# ENEL400_Project_2021-03-30.net
KiCad netlist of a schematic drawn in EasyEDA
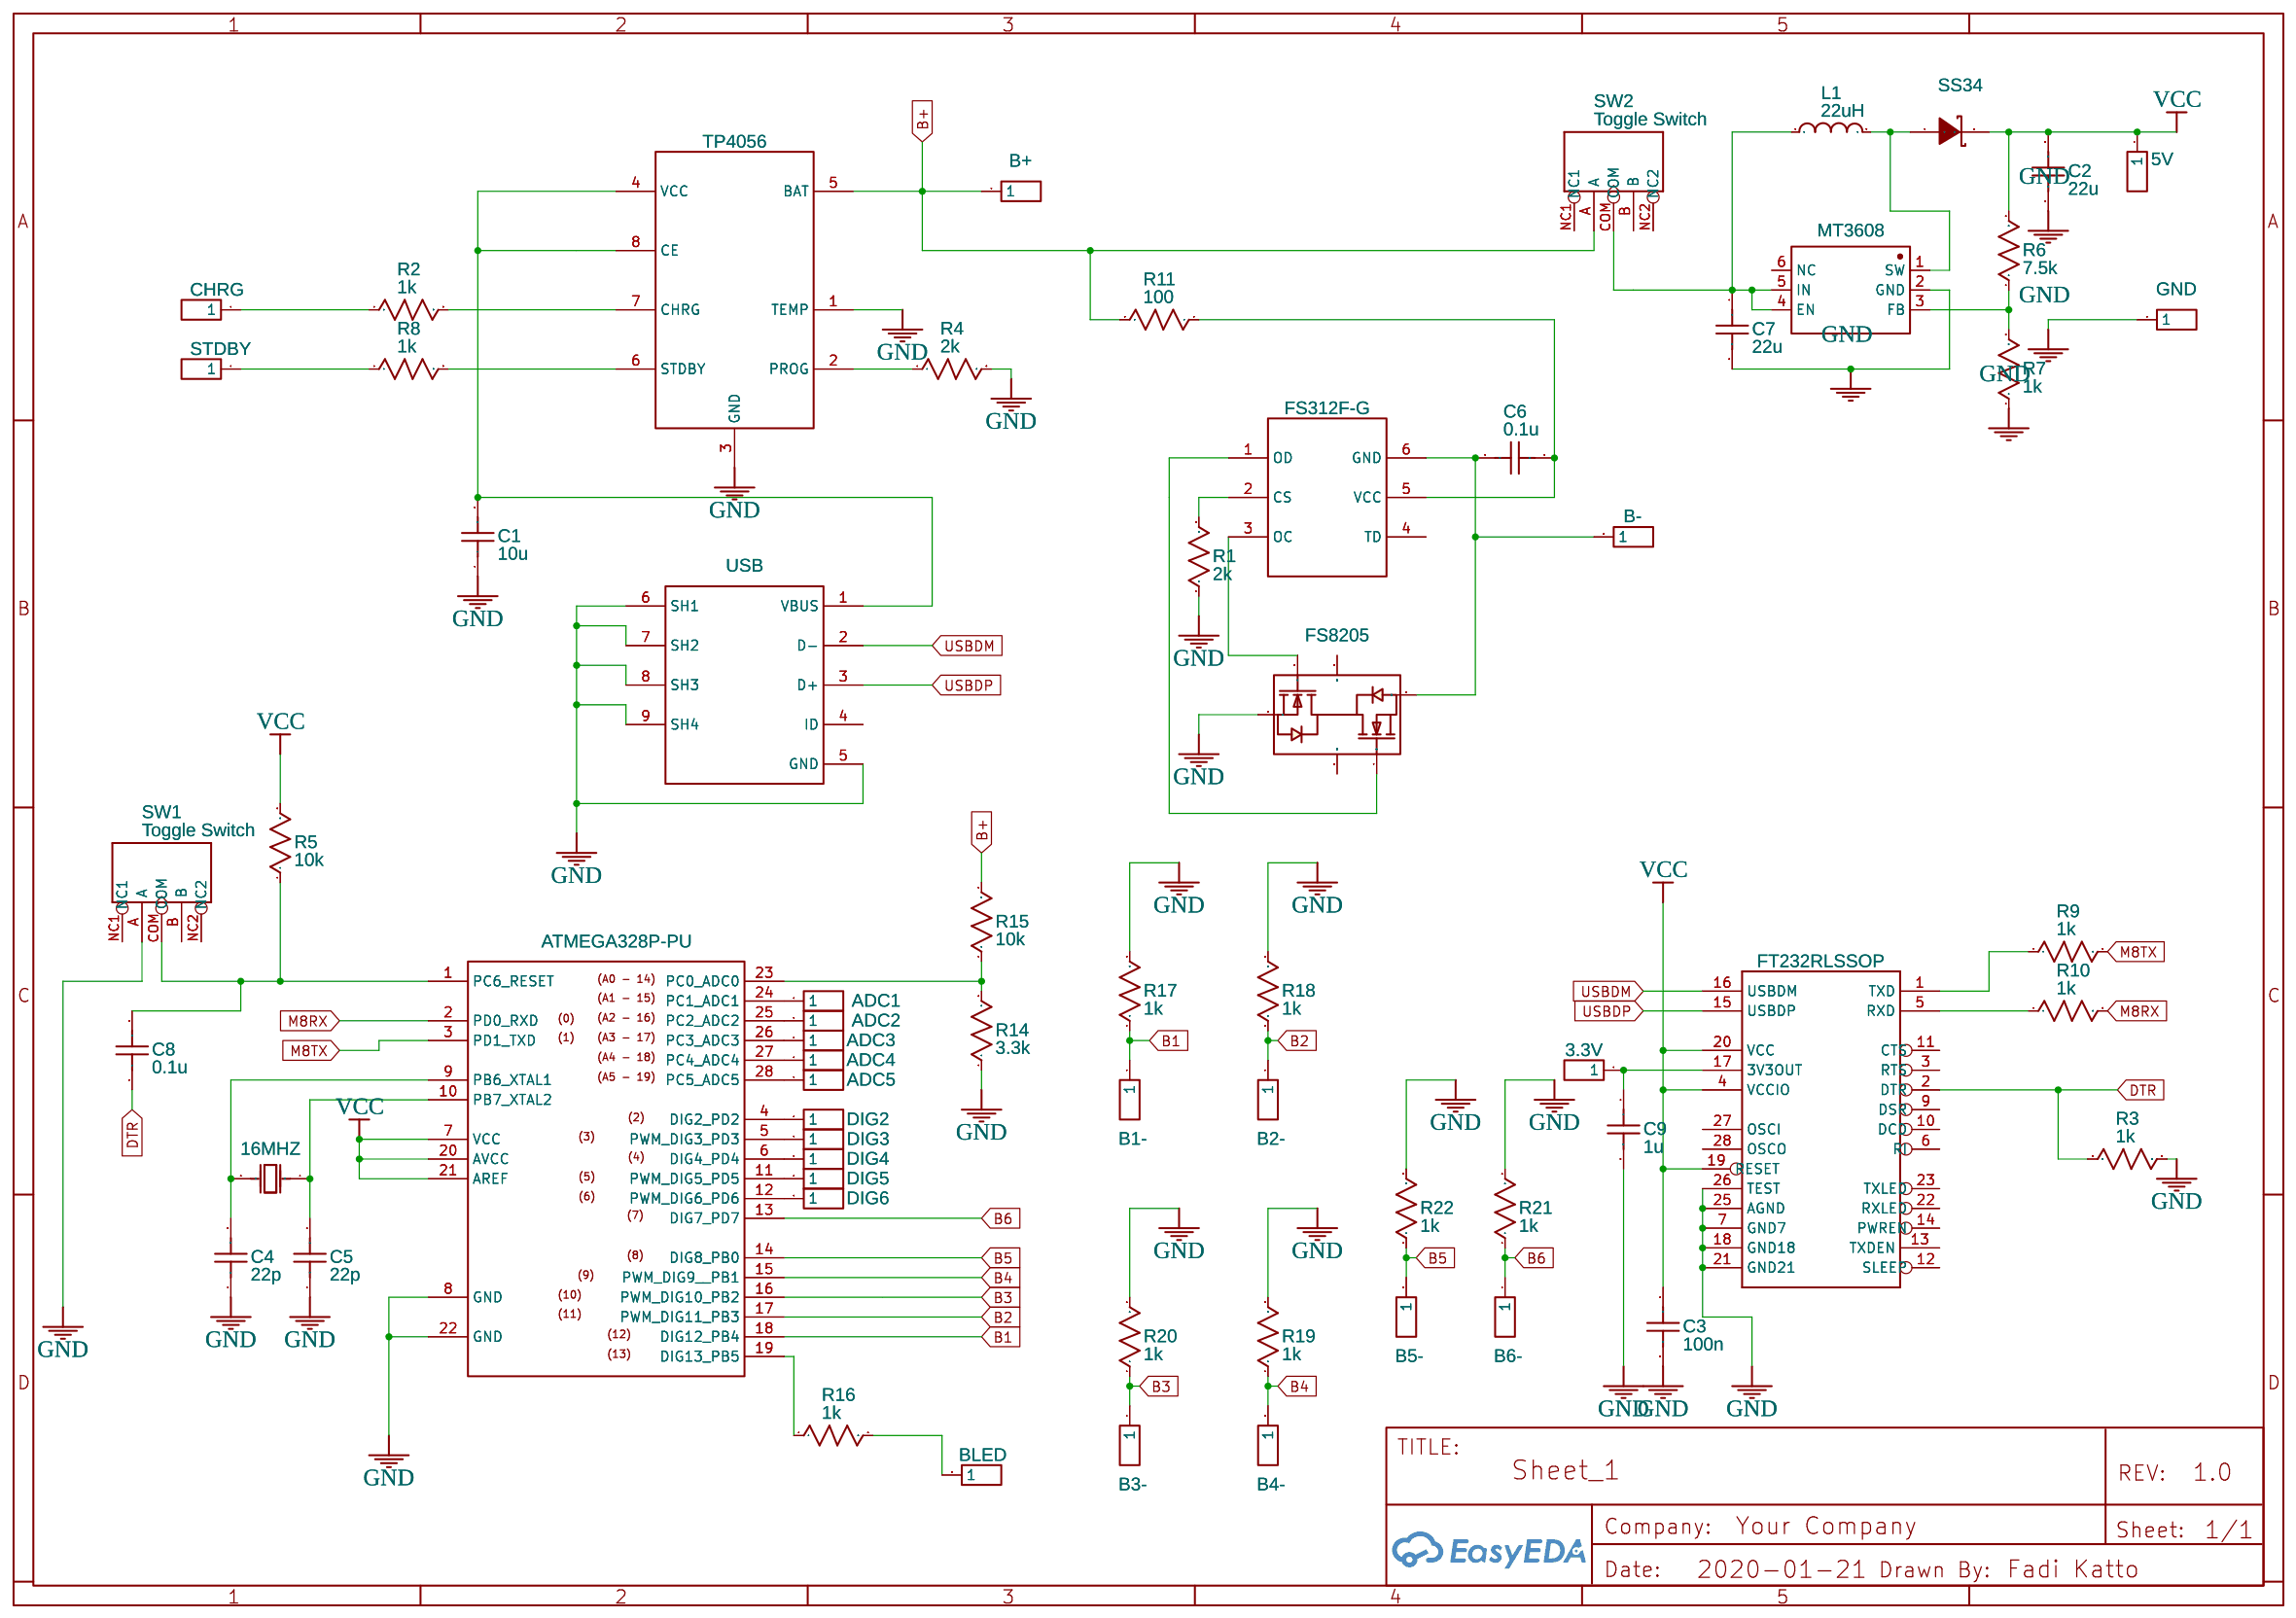
[diagram p0: schematic sheet]

(export (version "E")
  (design (tool "Eeschema 10.0.6"))
  (components
    (comp (ref "3.3V")
      (value "Header-Male-2.54_1x1")
      (fields (field (name "BOM_Supplier Part") "C81276"))
      (libsource (lib "") (part "Header-Male-2.54_1x1_4"))
    )
    (comp (ref "5V")
      (value "Header-Male-2.54_1x1")
      (fields (field (name "BOM_Supplier Part") "C81276"))
      (libsource (lib "") (part "Header-Male-2.54_1x1_3"))
    )
    (comp (ref "16MHZ")
      (value "16MHZ")
      (fields
        (field (name "BOM_Manufacturer Part") "X49SD16MSD2SC")
        (field (name "BOM_Supplier Part") "C16212")
      )
      (libsource (lib "") (part "16MHZ"))
    )
    (comp (ref "ADC1")
      (value "Header-Male-2.54_1x1")
      (fields (field (name "BOM_Supplier Part") "C81276"))
      (libsource (lib "") (part "Header-Male-2.54_1x1"))
    )
    (comp (ref "ADC2")
      (value "Header-Male-2.54_1x1")
      (fields (field (name "BOM_Supplier Part") "C81276"))
      (libsource (lib "") (part "Header-Male-2.54_1x1"))
    )
    (comp (ref "ADC3")
      (value "Header-Male-2.54_1x1")
      (fields (field (name "BOM_Supplier Part") "C81276"))
      (libsource (lib "") (part "Header-Male-2.54_1x1"))
    )
    (comp (ref "ADC4")
      (value "Header-Male-2.54_1x1")
      (fields (field (name "BOM_Supplier Part") "C81276"))
      (libsource (lib "") (part "Header-Male-2.54_1x1"))
    )
    (comp (ref "ADC5")
      (value "Header-Male-2.54_1x1")
      (fields (field (name "BOM_Supplier Part") "C81276"))
      (libsource (lib "") (part "Header-Male-2.54_1x1"))
    )
    (comp (ref "ATMEGA328P-PU")
      (value "ATMEGA328P-PU")
      (fields (field (name "BOM_Supplier Part") "C33901"))
      (libsource (lib "") (part "ATMEGA328P-PU"))
    )
    (comp (ref "B+")
      (value "Header-Male-2.54_1x1")
      (fields (field (name "BOM_Supplier Part") "C81276"))
      (libsource (lib "") (part "Header-Male-2.54_1x1_14"))
    )
    (comp (ref "B-")
      (value "Header-Male-2.54_1x1")
      (fields (field (name "BOM_Supplier Part") "C81276"))
      (libsource (lib "") (part "Header-Male-2.54_1x1_6"))
    )
    (comp (ref "B1-")
      (value "Header-Male-2.54_1x1")
      (fields (field (name "BOM_Supplier Part") "C81276"))
      (libsource (lib "") (part "Header-Male-2.54_1x1_8"))
    )
    (comp (ref "B2-")
      (value "Header-Male-2.54_1x1")
      (fields (field (name "BOM_Supplier Part") "C81276"))
      (libsource (lib "") (part "Header-Male-2.54_1x1_5"))
    )
    (comp (ref "B3-")
      (value "Header-Male-2.54_1x1")
      (fields (field (name "BOM_Supplier Part") "C81276"))
      (libsource (lib "") (part "Header-Male-2.54_1x1_7"))
    )
    (comp (ref "B4-")
      (value "Header-Male-2.54_1x1")
      (fields (field (name "BOM_Supplier Part") "C81276"))
      (libsource (lib "") (part "Header-Male-2.54_1x1_2"))
    )
    (comp (ref "B5-")
      (value "Header-Male-2.54_1x1")
      (fields (field (name "BOM_Supplier Part") "C81276"))
      (libsource (lib "") (part "Header-Male-2.54_1x1_10"))
    )
    (comp (ref "B6-")
      (value "Header-Male-2.54_1x1")
      (fields (field (name "BOM_Supplier Part") "C81276"))
      (libsource (lib "") (part "Header-Male-2.54_1x1_12"))
    )
    (comp (ref "BLED")
      (value "Header-Male-2.54_1x1")
      (fields (field (name "BOM_Supplier Part") "C81276"))
      (libsource (lib "") (part "Header-Male-2.54_1x1_15"))
    )
    (comp (ref "C1") (value "10u") (libsource (lib "") (part "Cap_0805_US_1")))
    (comp (ref "C2") (value "22u") (libsource (lib "") (part "Cap_0805_US_1")))
    (comp (ref "C3") (value "100n") (libsource (lib "") (part "Cap_0805_US")))
    (comp (ref "C4") (value "22p") (libsource (lib "") (part "Cap_0805_US_1")))
    (comp (ref "C5") (value "22p") (libsource (lib "") (part "Cap_0805_US_1")))
    (comp (ref "C6") (value "0.1u") (libsource (lib "") (part "Cap_0805_US_2")))
    (comp (ref "C7") (value "22u") (libsource (lib "") (part "Cap_0805_US")))
    (comp (ref "C8") (value "0.1u") (libsource (lib "") (part "Cap_0805_US_1")))
    (comp (ref "C9") (value "1u") (libsource (lib "") (part "Cap_0805_US")))
    (comp (ref "CHRG")
      (value "Header-Male-2.54_1x1")
      (fields (field (name "BOM_Supplier Part") "C81276"))
      (libsource (lib "") (part "Header-Male-2.54_1x1_13"))
    )
    (comp (ref "DIG2")
      (value "Header-Male-2.54_1x1")
      (fields (field (name "BOM_Supplier Part") "C81276"))
      (libsource (lib "") (part "Header-Male-2.54_1x1_1"))
    )
    (comp (ref "DIG3")
      (value "Header-Male-2.54_1x1")
      (fields (field (name "BOM_Supplier Part") "C81276"))
      (libsource (lib "") (part "Header-Male-2.54_1x1_1"))
    )
    (comp (ref "DIG4")
      (value "Header-Male-2.54_1x1")
      (fields (field (name "BOM_Supplier Part") "C81276"))
      (libsource (lib "") (part "Header-Male-2.54_1x1_1"))
    )
    (comp (ref "DIG5")
      (value "Header-Male-2.54_1x1")
      (fields (field (name "BOM_Supplier Part") "C81276"))
      (libsource (lib "") (part "Header-Male-2.54_1x1_1"))
    )
    (comp (ref "DIG6")
      (value "Header-Male-2.54_1x1")
      (fields (field (name "BOM_Supplier Part") "C81276"))
      (libsource (lib "") (part "Header-Male-2.54_1x1_1"))
    )
    (comp (ref "FS312F-G")
      (value "FS312F-G")
      (fields (field (name "BOM_Manufacturer Part") "DW01+G") (field (name "BOM_Supplier Part") "C14213"))
      (libsource (lib "") (part "Unknown_690_-525"))
    )
    (comp (ref "FS8205")
      (value "FS8205")
      (fields (field (name "BOM_Supplier Part") "C32254"))
      (libsource (lib "") (part "Unknown_725_-375"))
    )
    (comp (ref "FT232RLSSOP") (value "FT232RLSSOP") (libsource (lib "") (part "FT232RLSSOP")))
    (comp (ref "GND")
      (value "Header-Male-2.54_1x1")
      (fields (field (name "BOM_Supplier Part") "C81276"))
      (libsource (lib "") (part "Header-Male-2.54_1x1_11"))
    )
    (comp (ref "L1") (value "22uH") (libsource (lib "") (part "Inductor_0805_US")))
    (comp (ref "MT3608")
      (value "MT3608")
      (fields (field (name "BOM_Supplier Part") "C84817"))
      (libsource (lib "") (part "Unknown_995_-610"))
    )
    (comp (ref "R1") (value "2k") (libsource (lib "") (part "Res_0805(1/8W)_US")))
    (comp (ref "R2") (value "1k") (libsource (lib "") (part "Res_0805(1/8W)_US_1")))
    (comp (ref "R3") (value "1k") (libsource (lib "") (part "Res_0805(1/8W)_US_1")))
    (comp (ref "R4") (value "2k") (libsource (lib "") (part "Res_0805(1/8W)_US_1")))
    (comp (ref "R5") (value "10k") (libsource (lib "") (part "Res_0805(1/8W)_US")))
    (comp (ref "R6") (value "7.5k") (libsource (lib "") (part "Res_0805(1/8W)_US")))
    (comp (ref "R7") (value "1k") (libsource (lib "") (part "Res_0805(1/8W)_US")))
    (comp (ref "R8") (value "1k") (libsource (lib "") (part "Res_0805(1/8W)_US_1")))
    (comp (ref "R9") (value "1k") (libsource (lib "") (part "Res_0805(1/8W)_US_1")))
    (comp (ref "R10") (value "1k") (libsource (lib "") (part "Res_0805(1/8W)_US_1")))
    (comp (ref "R11") (value "100") (libsource (lib "") (part "Res_0805(1/8W)_US_2")))
    (comp (ref "R14") (value "3.3k") (libsource (lib "") (part "Res_0805(1/8W)_US")))
    (comp (ref "R15") (value "10k") (libsource (lib "") (part "Res_0805(1/8W)_US")))
    (comp (ref "R16") (value "1k") (libsource (lib "") (part "Res_0805(1/8W)_US_1")))
    (comp (ref "R17") (value "1k") (libsource (lib "") (part "Res_0805(1/8W)_US")))
    (comp (ref "R18") (value "1k") (libsource (lib "") (part "Res_0805(1/8W)_US")))
    (comp (ref "R19") (value "1k") (libsource (lib "") (part "Res_0805(1/8W)_US")))
    (comp (ref "R20") (value "1k") (libsource (lib "") (part "Res_0805(1/8W)_US")))
    (comp (ref "R21") (value "1k") (libsource (lib "") (part "Res_0805(1/8W)_US")))
    (comp (ref "R22") (value "1k") (libsource (lib "") (part "Res_0805(1/8W)_US")))
    (comp (ref "SS34")
      (value "SS34")
      (fields (field (name "BOM_Supplier Part") "C8678"))
      (libsource (lib "") (part "Unknown_1035_-670"))
    )
    (comp (ref "STDBY")
      (value "Header-Male-2.54_1x1")
      (fields (field (name "BOM_Supplier Part") "C81276"))
      (libsource (lib "") (part "Header-Male-2.54_1x1_9"))
    )
    (comp (ref "SW1")
      (value "Toggle Switch")
      (fields (field (name "BOM_Manufacturer Part") "3P-2.0-90D-REINFORCE;"))
      (libsource (lib "") (part "Unknown_130_-300"))
    )
    (comp (ref "SW2")
      (value "Toggle Switch")
      (fields (field (name "BOM_Manufacturer Part") "3P-2.0-90D-REINFORCE;"))
      (libsource (lib "") (part "Unknown_865_-660"))
    )
    (comp (ref "TP4056")
      (value "TP4056")
      (fields (field (name "BOM_Supplier Part") "C16581"))
      (libsource (lib "") (part "Unknown_420_-580"))
    )
    (comp (ref "USB") (value "USB - Mini USB") (libsource (lib "") (part "USB - Mini USB")))
  )
  (nets
    (net (code "1") (name "B+") (class "Default")
      (node (ref "B+") (pin "1") (pinfunction "1_1") (pintype "input"))
      (node (ref "R11") (pin "2") (pinfunction "2_2") (pintype "unspecified"))
      (node (ref "R15") (pin "2") (pinfunction "2_2") (pintype "unspecified"))
      (node (ref "SW2") (pin "A") (pinfunction "A_A") (pintype "unspecified"))
      (node (ref "TP4056") (pin "5") (pinfunction "BAT_5") (pintype "unspecified"))
    )
    (net (code "2") (name "B1") (class "Default")
      (node (ref "ATMEGA328P-PU") (pin "18") (pinfunction "DIG12_PB4_18") (pintype "bidirectional"))
      (node (ref "B1-") (pin "1") (pinfunction "1_1") (pintype "input"))
      (node (ref "R17") (pin "1") (pinfunction "1_1") (pintype "unspecified"))
    )
    (net (code "3") (name "B2") (class "Default")
      (node (ref "ATMEGA328P-PU") (pin "17") (pinfunction "PWM_DIG11_PB3_17") (pintype "bidirectional"))
      (node (ref "B2-") (pin "1") (pinfunction "1_1") (pintype "input"))
      (node (ref "R18") (pin "1") (pinfunction "1_1") (pintype "unspecified"))
    )
    (net (code "4") (name "B3") (class "Default")
      (node (ref "ATMEGA328P-PU") (pin "16") (pinfunction "PWM_DIG10_PB2_16") (pintype "bidirectional"))
      (node (ref "B3-") (pin "1") (pinfunction "1_1") (pintype "input"))
      (node (ref "R20") (pin "1") (pinfunction "1_1") (pintype "unspecified"))
    )
    (net (code "5") (name "B4") (class "Default")
      (node (ref "ATMEGA328P-PU") (pin "15") (pinfunction "PWM_DIG9__PB1_15") (pintype "bidirectional"))
      (node (ref "B4-") (pin "1") (pinfunction "1_1") (pintype "input"))
      (node (ref "R19") (pin "1") (pinfunction "1_1") (pintype "unspecified"))
    )
    (net (code "6") (name "B5") (class "Default")
      (node (ref "ATMEGA328P-PU") (pin "14") (pinfunction "DIG8_PB0_14") (pintype "bidirectional"))
      (node (ref "B5-") (pin "1") (pinfunction "1_1") (pintype "input"))
      (node (ref "R22") (pin "1") (pinfunction "1_1") (pintype "unspecified"))
    )
    (net (code "7") (name "B6") (class "Default")
      (node (ref "ATMEGA328P-PU") (pin "13") (pinfunction "DIG7_PD7_13") (pintype "bidirectional"))
      (node (ref "B6-") (pin "1") (pinfunction "1_1") (pintype "input"))
      (node (ref "R21") (pin "1") (pinfunction "1_1") (pintype "unspecified"))
    )
    (net (code "8") (name "DTR") (class "Default")
      (node (ref "C8") (pin "1") (pinfunction "1_1") (pintype "unspecified"))
      (node (ref "FT232RLSSOP") (pin "2") (pinfunction "DTR_2") (pintype "output"))
      (node (ref "R3") (pin "1") (pinfunction "1_1") (pintype "unspecified"))
    )
    (net (code "9") (name "GND") (class "Default")
      (node (ref "ATMEGA328P-PU") (pin "22") (pinfunction "GND_22") (pintype "passive"))
      (node (ref "ATMEGA328P-PU") (pin "8") (pinfunction "GND_8") (pintype "passive"))
      (node (ref "C1") (pin "1") (pinfunction "1_1") (pintype "unspecified"))
      (node (ref "C2") (pin "1") (pinfunction "1_1") (pintype "unspecified"))
      (node (ref "C3") (pin "2") (pinfunction "2_2") (pintype "unspecified"))
      (node (ref "C4") (pin "1") (pinfunction "1_1") (pintype "unspecified"))
      (node (ref "C5") (pin "1") (pinfunction "1_1") (pintype "unspecified"))
      (node (ref "C7") (pin "2") (pinfunction "2_2") (pintype "unspecified"))
      (node (ref "C9") (pin "2") (pinfunction "2_2") (pintype "unspecified"))
      (node (ref "FS8205") (pin "1") (pinfunction "S1_1") (pintype "unspecified"))
      (node (ref "FT232RLSSOP") (pin "18") (pinfunction "GND18_18") (pintype "passive"))
      (node (ref "FT232RLSSOP") (pin "21") (pinfunction "GND21_21") (pintype "passive"))
      (node (ref "FT232RLSSOP") (pin "25") (pinfunction "AGND_25") (pintype "passive"))
      (node (ref "FT232RLSSOP") (pin "26") (pinfunction "TEST_26") (pintype "input"))
      (node (ref "FT232RLSSOP") (pin "7") (pinfunction "GND7_7") (pintype "passive"))
      (node (ref "GND") (pin "1") (pinfunction "1_1") (pintype "input"))
      (node (ref "MT3608") (pin "2") (pinfunction "GND_2") (pintype "unspecified"))
      (node (ref "R1") (pin "1") (pinfunction "1_1") (pintype "unspecified"))
      (node (ref "R14") (pin "1") (pinfunction "1_1") (pintype "unspecified"))
      (node (ref "R17") (pin "2") (pinfunction "2_2") (pintype "unspecified"))
      (node (ref "R18") (pin "2") (pinfunction "2_2") (pintype "unspecified"))
      (node (ref "R19") (pin "2") (pinfunction "2_2") (pintype "unspecified"))
      (node (ref "R20") (pin "2") (pinfunction "2_2") (pintype "unspecified"))
      (node (ref "R21") (pin "2") (pinfunction "2_2") (pintype "unspecified"))
      (node (ref "R22") (pin "2") (pinfunction "2_2") (pintype "unspecified"))
      (node (ref "R3") (pin "2") (pinfunction "2_2") (pintype "unspecified"))
      (node (ref "R4") (pin "2") (pinfunction "2_2") (pintype "unspecified"))
      (node (ref "R7") (pin "1") (pinfunction "1_1") (pintype "unspecified"))
      (node (ref "SW1") (pin "A") (pinfunction "A_A") (pintype "unspecified"))
      (node (ref "TP4056") (pin "1") (pinfunction "TEMP_1") (pintype "unspecified"))
      (node (ref "TP4056") (pin "3") (pinfunction "GND_3") (pintype "unspecified"))
      (node (ref "USB") (pin "5") (pinfunction "GND_5") (pintype "passive"))
      (node (ref "USB") (pin "6") (pinfunction "SH1_6") (pintype "passive"))
      (node (ref "USB") (pin "7") (pinfunction "SH2_7") (pintype "passive"))
      (node (ref "USB") (pin "8") (pinfunction "SH3_8") (pintype "passive"))
      (node (ref "USB") (pin "9") (pinfunction "SH4_9") (pintype "passive"))
    )
    (net (code "10") (name "M8RX") (class "Default")
      (node (ref "ATMEGA328P-PU") (pin "2") (pinfunction "PD0_RXD_2") (pintype "bidirectional"))
      (node (ref "R10") (pin "2") (pinfunction "2_2") (pintype "unspecified"))
    )
    (net (code "11") (name "M8TX") (class "Default")
      (node (ref "ATMEGA328P-PU") (pin "3") (pinfunction "PD1_TXD_3") (pintype "bidirectional"))
      (node (ref "R9") (pin "2") (pinfunction "2_2") (pintype "unspecified"))
    )
    (net (code "12") (name "Net-(16MHZ-OSC1)") (class "Default")
      (node (ref "16MHZ") (pin "1") (pinfunction "OSC1_1") (pintype "input"))
      (node (ref "ATMEGA328P-PU") (pin "10") (pinfunction "PB7_XTAL2_10") (pintype "bidirectional"))
      (node (ref "C5") (pin "2") (pinfunction "2_2") (pintype "unspecified"))
    )
    (net (code "13") (name "Net-(16MHZ-OSC2)") (class "Default")
      (node (ref "16MHZ") (pin "2") (pinfunction "OSC2_2") (pintype "input"))
      (node (ref "ATMEGA328P-PU") (pin "9") (pinfunction "PB6_XTAL1_9") (pintype "bidirectional"))
      (node (ref "C4") (pin "2") (pinfunction "2_2") (pintype "unspecified"))
    )
    (net (code "14") (name "Net-(ATMEGA328P-PU-DIG2_PD2)") (class "Default")
      (node (ref "ATMEGA328P-PU") (pin "4") (pinfunction "DIG2_PD2_4") (pintype "bidirectional"))
      (node (ref "DIG2") (pin "1") (pinfunction "1_1") (pintype "input"))
    )
    (net (code "15") (name "Net-(ATMEGA328P-PU-DIG4_PD4)") (class "Default")
      (node (ref "ATMEGA328P-PU") (pin "6") (pinfunction "DIG4_PD4_6") (pintype "bidirectional"))
      (node (ref "DIG4") (pin "1") (pinfunction "1_1") (pintype "input"))
    )
    (net (code "16") (name "Net-(ATMEGA328P-PU-DIG13_PB5)") (class "Default")
      (node (ref "ATMEGA328P-PU") (pin "19") (pinfunction "DIG13_PB5_19") (pintype "bidirectional"))
      (node (ref "R16") (pin "1") (pinfunction "1_1") (pintype "unspecified"))
    )
    (net (code "17") (name "Net-(ATMEGA328P-PU-PC0_ADC0)") (class "Default")
      (node (ref "ATMEGA328P-PU") (pin "23") (pinfunction "PC0_ADC0_23") (pintype "bidirectional"))
      (node (ref "R14") (pin "2") (pinfunction "2_2") (pintype "unspecified"))
      (node (ref "R15") (pin "1") (pinfunction "1_1") (pintype "unspecified"))
    )
    (net (code "18") (name "Net-(ATMEGA328P-PU-PC1_ADC1)") (class "Default")
      (node (ref "ADC1") (pin "1") (pinfunction "1_1") (pintype "input"))
      (node (ref "ATMEGA328P-PU") (pin "24") (pinfunction "PC1_ADC1_24") (pintype "bidirectional"))
    )
    (net (code "19") (name "Net-(ATMEGA328P-PU-PC2_ADC2)") (class "Default")
      (node (ref "ADC2") (pin "1") (pinfunction "1_1") (pintype "input"))
      (node (ref "ATMEGA328P-PU") (pin "25") (pinfunction "PC2_ADC2_25") (pintype "bidirectional"))
    )
    (net (code "20") (name "Net-(ATMEGA328P-PU-PC3_ADC3)") (class "Default")
      (node (ref "ADC3") (pin "1") (pinfunction "1_1") (pintype "input"))
      (node (ref "ATMEGA328P-PU") (pin "26") (pinfunction "PC3_ADC3_26") (pintype "bidirectional"))
    )
    (net (code "21") (name "Net-(ATMEGA328P-PU-PC4_ADC4)") (class "Default")
      (node (ref "ADC4") (pin "1") (pinfunction "1_1") (pintype "input"))
      (node (ref "ATMEGA328P-PU") (pin "27") (pinfunction "PC4_ADC4_27") (pintype "bidirectional"))
    )
    (net (code "22") (name "Net-(ATMEGA328P-PU-PC5_ADC5)") (class "Default")
      (node (ref "ADC5") (pin "1") (pinfunction "1_1") (pintype "input"))
      (node (ref "ATMEGA328P-PU") (pin "28") (pinfunction "PC5_ADC5_28") (pintype "bidirectional"))
    )
    (net (code "23") (name "Net-(ATMEGA328P-PU-PC6_RESET)") (class "Default")
      (node (ref "ATMEGA328P-PU") (pin "1") (pinfunction "PC6_RESET_1") (pintype "bidirectional"))
      (node (ref "C8") (pin "2") (pinfunction "2_2") (pintype "unspecified"))
      (node (ref "R5") (pin "1") (pinfunction "1_1") (pintype "unspecified"))
      (node (ref "SW1") (pin "COM") (pinfunction "COM_COM") (pintype "unspecified"))
    )
    (net (code "24") (name "Net-(ATMEGA328P-PU-PWM_DIG3_PD3)") (class "Default")
      (node (ref "ATMEGA328P-PU") (pin "5") (pinfunction "PWM_DIG3_PD3_5") (pintype "bidirectional"))
      (node (ref "DIG3") (pin "1") (pinfunction "1_1") (pintype "input"))
    )
    (net (code "25") (name "Net-(ATMEGA328P-PU-PWM_DIG5_PD5)") (class "Default")
      (node (ref "ATMEGA328P-PU") (pin "11") (pinfunction "PWM_DIG5_PD5_11") (pintype "bidirectional"))
      (node (ref "DIG5") (pin "1") (pinfunction "1_1") (pintype "input"))
    )
    (net (code "26") (name "Net-(ATMEGA328P-PU-PWM_DIG6_PD6)") (class "Default")
      (node (ref "ATMEGA328P-PU") (pin "12") (pinfunction "PWM_DIG6_PD6_12") (pintype "bidirectional"))
      (node (ref "DIG6") (pin "1") (pinfunction "1_1") (pintype "input"))
    )
    (net (code "27") (name "Net-(BLED-Pad1)") (class "Default")
      (node (ref "BLED") (pin "1") (pinfunction "1_1") (pintype "input"))
      (node (ref "R16") (pin "2") (pinfunction "2_2") (pintype "unspecified"))
    )
    (net (code "28") (name "Net-(CHRG-Pad1)") (class "Default")
      (node (ref "CHRG") (pin "1") (pinfunction "1_1") (pintype "input"))
      (node (ref "R2") (pin "1") (pinfunction "1_1") (pintype "unspecified"))
    )
    (net (code "29") (name "Net-(FS312F-G-CS)") (class "Default")
      (node (ref "FS312F-G") (pin "2") (pinfunction "CS_2") (pintype "unspecified"))
      (node (ref "R1") (pin "2") (pinfunction "2_2") (pintype "unspecified"))
    )
    (net (code "30") (name "Net-(FS312F-G-GND)") (class "Default")
      (node (ref "B-") (pin "1") (pinfunction "1_1") (pintype "input"))
      (node (ref "C6") (pin "2") (pinfunction "2_2") (pintype "unspecified"))
      (node (ref "FS312F-G") (pin "6") (pinfunction "GND_6") (pintype "unspecified"))
      (node (ref "FS8205") (pin "3") (pinfunction "S2_3") (pintype "unspecified"))
    )
    (net (code "31") (name "Net-(FS312F-G-OC)") (class "Default")
      (node (ref "FS312F-G") (pin "3") (pinfunction "OC_3") (pintype "unspecified"))
      (node (ref "FS8205") (pin "6") (pinfunction "G1_6") (pintype "unspecified"))
    )
    (net (code "32") (name "Net-(FS312F-G-OD)") (class "Default")
      (node (ref "FS312F-G") (pin "1") (pinfunction "OD_1") (pintype "unspecified"))
      (node (ref "FS8205") (pin "4") (pinfunction "G2_4") (pintype "unspecified"))
    )
    (net (code "33") (name "Net-(FS312F-G-VCC)") (class "Default")
      (node (ref "C6") (pin "1") (pinfunction "1_1") (pintype "unspecified"))
      (node (ref "FS312F-G") (pin "5") (pinfunction "VCC_5") (pintype "unspecified"))
      (node (ref "R11") (pin "1") (pinfunction "1_1") (pintype "unspecified"))
    )
    (net (code "34") (name "Net-(FT232RLSSOP-3V3OUT)") (class "Default")
      (node (ref "3.3V") (pin "1") (pinfunction "1_1") (pintype "input"))
      (node (ref "C9") (pin "1") (pinfunction "1_1") (pintype "unspecified"))
      (node (ref "FT232RLSSOP") (pin "17") (pinfunction "3V3OUT_17") (pintype "output"))
    )
    (net (code "35") (name "Net-(FT232RLSSOP-RXD)") (class "Default")
      (node (ref "FT232RLSSOP") (pin "5") (pinfunction "RXD_5") (pintype "input"))
      (node (ref "R10") (pin "1") (pinfunction "1_1") (pintype "unspecified"))
    )
    (net (code "36") (name "Net-(FT232RLSSOP-TXD)") (class "Default")
      (node (ref "FT232RLSSOP") (pin "1") (pinfunction "TXD_1") (pintype "output"))
      (node (ref "R9") (pin "1") (pinfunction "1_1") (pintype "unspecified"))
    )
    (net (code "37") (name "Net-(MT3608-EN)") (class "Default")
      (node (ref "C7") (pin "1") (pinfunction "1_1") (pintype "unspecified"))
      (node (ref "L1") (pin "1") (pinfunction "1_1") (pintype "unspecified"))
      (node (ref "MT3608") (pin "4") (pinfunction "EN_4") (pintype "unspecified"))
      (node (ref "MT3608") (pin "5") (pinfunction "IN_5") (pintype "unspecified"))
      (node (ref "SW2") (pin "COM") (pinfunction "COM_COM") (pintype "unspecified"))
    )
    (net (code "38") (name "Net-(MT3608-FB)") (class "Default")
      (node (ref "MT3608") (pin "3") (pinfunction "FB_3") (pintype "unspecified"))
      (node (ref "R6") (pin "1") (pinfunction "1_1") (pintype "unspecified"))
      (node (ref "R7") (pin "2") (pinfunction "2_2") (pintype "unspecified"))
    )
    (net (code "39") (name "Net-(MT3608-SW)") (class "Default")
      (node (ref "L1") (pin "2") (pinfunction "2_2") (pintype "unspecified"))
      (node (ref "MT3608") (pin "1") (pinfunction "SW_1") (pintype "unspecified"))
      (node (ref "SS34") (pin "1") (pinfunction "A_1") (pintype "unspecified"))
    )
    (net (code "40") (name "Net-(R8-Pad1)") (class "Default")
      (node (ref "R8") (pin "1") (pinfunction "1_1") (pintype "unspecified"))
      (node (ref "STDBY") (pin "1") (pinfunction "1_1") (pintype "input"))
    )
    (net (code "41") (name "Net-(TP4056-CE)") (class "Default")
      (node (ref "C1") (pin "2") (pinfunction "2_2") (pintype "unspecified"))
      (node (ref "TP4056") (pin "4") (pinfunction "VCC_4") (pintype "unspecified"))
      (node (ref "TP4056") (pin "8") (pinfunction "CE_8") (pintype "unspecified"))
      (node (ref "USB") (pin "1") (pinfunction "VBUS_1") (pintype "passive"))
    )
    (net (code "42") (name "Net-(TP4056-CHRG)") (class "Default")
      (node (ref "R2") (pin "2") (pinfunction "2_2") (pintype "unspecified"))
      (node (ref "TP4056") (pin "7") (pinfunction "CHRG_7") (pintype "unspecified"))
    )
    (net (code "43") (name "Net-(TP4056-PROG)") (class "Default")
      (node (ref "R4") (pin "1") (pinfunction "1_1") (pintype "unspecified"))
      (node (ref "TP4056") (pin "2") (pinfunction "PROG_2") (pintype "unspecified"))
    )
    (net (code "44") (name "Net-(TP4056-STDBY)") (class "Default")
      (node (ref "R8") (pin "2") (pinfunction "2_2") (pintype "unspecified"))
      (node (ref "TP4056") (pin "6") (pinfunction "STDBY_6") (pintype "unspecified"))
    )
    (net (code "45") (name "USBDM") (class "Default")
      (node (ref "FT232RLSSOP") (pin "16") (pinfunction "USBDM_16") (pintype "unspecified"))
      (node (ref "USB") (pin "2") (pinfunction "D-_2") (pintype "bidirectional"))
    )
    (net (code "46") (name "USBDP") (class "Default")
      (node (ref "FT232RLSSOP") (pin "15") (pinfunction "USBDP_15") (pintype "unspecified"))
      (node (ref "USB") (pin "3") (pinfunction "D+_3") (pintype "bidirectional"))
    )
    (net (code "47") (name "VCC") (class "Default")
      (node (ref "5V") (pin "1") (pinfunction "1_1") (pintype "input"))
      (node (ref "ATMEGA328P-PU") (pin "20") (pinfunction "AVCC_20") (pintype "passive"))
      (node (ref "ATMEGA328P-PU") (pin "21") (pinfunction "AREF_21") (pintype "passive"))
      (node (ref "ATMEGA328P-PU") (pin "7") (pinfunction "VCC_7") (pintype "passive"))
      (node (ref "C2") (pin "2") (pinfunction "2_2") (pintype "unspecified"))
      (node (ref "C3") (pin "1") (pinfunction "1_1") (pintype "unspecified"))
      (node (ref "FT232RLSSOP") (pin "19") (pinfunction "RESET_19") (pintype "input"))
      (node (ref "FT232RLSSOP") (pin "20") (pinfunction "VCC_20") (pintype "passive"))
      (node (ref "FT232RLSSOP") (pin "4") (pinfunction "VCCIO_4") (pintype "passive"))
      (node (ref "R5") (pin "2") (pinfunction "2_2") (pintype "unspecified"))
      (node (ref "R6") (pin "2") (pinfunction "2_2") (pintype "unspecified"))
      (node (ref "SS34") (pin "2") (pinfunction "K_2") (pintype "unspecified"))
    )
    (net (code "48") (name "unconnected-(FS312F-G-TD-Pad4)") (class "Default")
      (node (ref "FS312F-G") (pin "4") (pinfunction "TD_4") (pintype "unspecified"))
    )
    (net (code "49") (name "unconnected-(FS8205-D12-Pad2)") (class "Default")
      (node (ref "FS8205") (pin "2") (pinfunction "D12_2") (pintype "unspecified"))
    )
    (net (code "50") (name "unconnected-(FS8205-D12-Pad5)") (class "Default")
      (node (ref "FS8205") (pin "5") (pinfunction "D12_5") (pintype "unspecified"))
    )
    (net (code "51") (name "unconnected-(FT232RLSSOP-CTS-Pad11)") (class "Default")
      (node (ref "FT232RLSSOP") (pin "11") (pinfunction "CTS_11") (pintype "input"))
    )
    (net (code "52") (name "unconnected-(FT232RLSSOP-DCD-Pad10)") (class "Default")
      (node (ref "FT232RLSSOP") (pin "10") (pinfunction "DCD_10") (pintype "input"))
    )
    (net (code "53") (name "unconnected-(FT232RLSSOP-DSR-Pad9)") (class "Default")
      (node (ref "FT232RLSSOP") (pin "9") (pinfunction "DSR_9") (pintype "input"))
    )
    (net (code "54") (name "unconnected-(FT232RLSSOP-OSCI-Pad27)") (class "Default")
      (node (ref "FT232RLSSOP") (pin "27") (pinfunction "OSCI_27") (pintype "input"))
    )
    (net (code "55") (name "unconnected-(FT232RLSSOP-OSCO-Pad28)") (class "Default")
      (node (ref "FT232RLSSOP") (pin "28") (pinfunction "OSCO_28") (pintype "output"))
    )
    (net (code "56") (name "unconnected-(FT232RLSSOP-PWREN-Pad14)") (class "Default")
      (node (ref "FT232RLSSOP") (pin "14") (pinfunction "PWREN_14") (pintype "input"))
    )
    (net (code "57") (name "unconnected-(FT232RLSSOP-RI-Pad6)") (class "Default")
      (node (ref "FT232RLSSOP") (pin "6") (pinfunction "RI_6") (pintype "input"))
    )
    (net (code "58") (name "unconnected-(FT232RLSSOP-RTS-Pad3)") (class "Default")
      (node (ref "FT232RLSSOP") (pin "3") (pinfunction "RTS_3") (pintype "output"))
    )
    (net (code "59") (name "unconnected-(FT232RLSSOP-RXLED-Pad22)") (class "Default")
      (node (ref "FT232RLSSOP") (pin "22") (pinfunction "RXLED_22") (pintype "input"))
    )
    (net (code "60") (name "unconnected-(FT232RLSSOP-SLEEP-Pad12)") (class "Default")
      (node (ref "FT232RLSSOP") (pin "12") (pinfunction "SLEEP_12") (pintype "input"))
    )
    (net (code "61") (name "unconnected-(FT232RLSSOP-TXDEN-Pad13)") (class "Default")
      (node (ref "FT232RLSSOP") (pin "13") (pinfunction "TXDEN_13") (pintype "input"))
    )
    (net (code "62") (name "unconnected-(FT232RLSSOP-TXLED-Pad23)") (class "Default")
      (node (ref "FT232RLSSOP") (pin "23") (pinfunction "TXLED_23") (pintype "input"))
    )
    (net (code "63") (name "unconnected-(MT3608-NC-Pad6)") (class "Default")
      (node (ref "MT3608") (pin "6") (pinfunction "NC_6") (pintype "unspecified"))
    )
    (net (code "64") (name "unconnected-(SW1-PadB)") (class "Default")
      (node (ref "SW1") (pin "B") (pinfunction "B_B") (pintype "unspecified"))
    )
    (net (code "65") (name "unconnected-(SW1-PadNC1)") (class "Default")
      (node (ref "SW1") (pin "NC1") (pinfunction "NC1_NC1") (pintype "unspecified"))
    )
    (net (code "66") (name "unconnected-(SW1-PadNC2)") (class "Default")
      (node (ref "SW1") (pin "NC2") (pinfunction "NC2_NC2") (pintype "unspecified"))
    )
    (net (code "67") (name "unconnected-(SW2-PadB)") (class "Default")
      (node (ref "SW2") (pin "B") (pinfunction "B_B") (pintype "unspecified"))
    )
    (net (code "68") (name "unconnected-(SW2-PadNC1)") (class "Default")
      (node (ref "SW2") (pin "NC1") (pinfunction "NC1_NC1") (pintype "unspecified"))
    )
    (net (code "69") (name "unconnected-(SW2-PadNC2)") (class "Default")
      (node (ref "SW2") (pin "NC2") (pinfunction "NC2_NC2") (pintype "unspecified"))
    )
    (net (code "70") (name "unconnected-(USB-ID-Pad4)") (class "Default")
      (node (ref "USB") (pin "4") (pinfunction "ID_4") (pintype "bidirectional"))
    )
  )
)
